# N303-3V1_0.net
KiCad netlist of a schematic drawn in Altium Designer
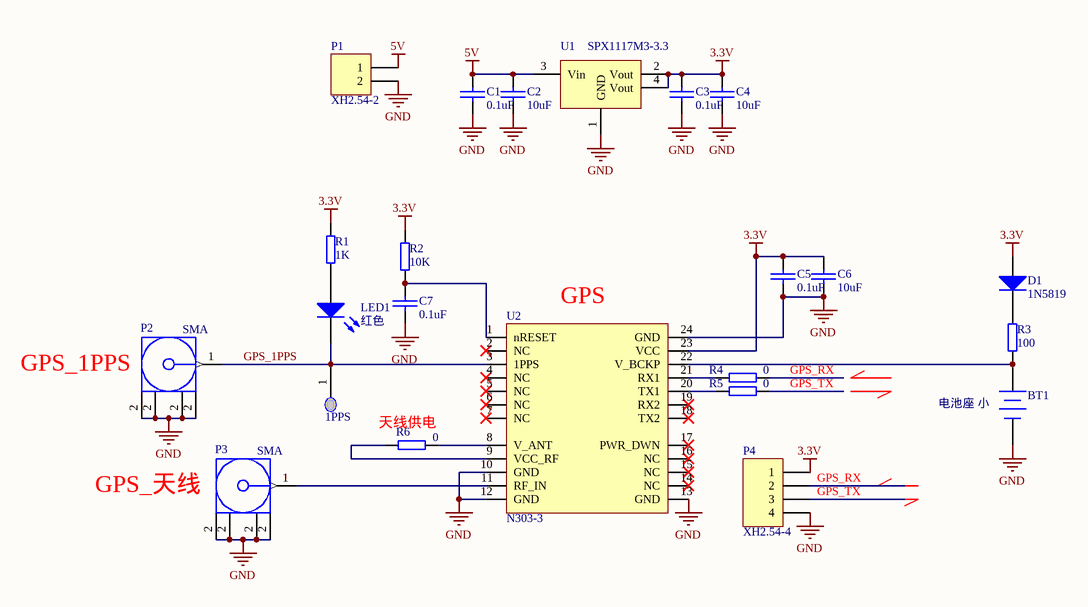
[diagram p0: N303-3V1.0.schdoc]

(export (version "E")
  (design (tool "Eeschema 10.0.6"))
  (components
    (comp (ref "1PPS")
      (value "TEST")
      (footprint "测试点（圆形）")
      (libsource (lib "Sch_Device_veryaz") (part "测试点_小"))
    )
    (comp (ref "BT1")
      (value "电池座 小")
      (footprint "电池座 2032 贴片 BS-8")
      (fields (field (name "PUBLISHER") "Altium Limited"))
      (libsource (lib "Sch_Device_veryaz") (part "电池座 小"))
    )
    (comp (ref "C1")
      (value "0.1uF")
      (footprint "0805")
      (libsource (lib "Sch_Device_veryaz") (part "电容 贴片 0805"))
    )
    (comp (ref "C2")
      (value "10uF")
      (footprint "1206")
      (libsource (lib "Sch_Device_veryaz") (part "电容 贴片 0805"))
    )
    (comp (ref "C3")
      (value "0.1uF")
      (footprint "0805")
      (libsource (lib "Sch_Device_veryaz") (part "电容 贴片 0805"))
    )
    (comp (ref "C4")
      (value "10uF")
      (footprint "1206")
      (libsource (lib "Sch_Device_veryaz") (part "电容 贴片 0805"))
    )
    (comp (ref "C5")
      (value "0.1uF")
      (footprint "0805")
      (libsource (lib "Sch_Device_veryaz") (part "电容 贴片 0805"))
    )
    (comp (ref "C6")
      (value "10uF")
      (footprint "1206")
      (libsource (lib "Sch_Device_veryaz") (part "电容 贴片 0805"))
    )
    (comp (ref "C7")
      (value "0.1uF")
      (footprint "0805")
      (libsource (lib "Sch_Device_veryaz") (part "电容 贴片 0805"))
    )
    (comp (ref "D1")
      (value "1N5819")
      (footprint "二极管 贴片 IN4148")
      (libsource (lib "Sch_Device_veryaz") (part "二极管 贴片 1N4148"))
    )
    (comp (ref "LED1")
      (value "红色")
      (footprint "LED5_单色")
      (libsource (lib "Sch_Device_veryaz") (part "贴片发光二极管 0805"))
    )
    (comp (ref "P1")
      (value "XH2.54-2")
      (footprint "VH2.54_2")
      (libsource (lib "Sch_Device_veryaz") (part "连接件 XH2.54-2"))
    )
    (comp (ref "P2")
      (value "SMA")
      (footprint "天线座 50ohm 直立")
      (libsource (lib "Sch_Device_veryaz") (part "联结件 天线座 SMA"))
    )
    (comp (ref "P3")
      (value "SMA")
      (footprint "天线座 50ohm 直立")
      (libsource (lib "Sch_Device_veryaz") (part "联结件 天线座 SMA"))
    )
    (comp (ref "P4")
      (value "XH2.54-4")
      (footprint "VH2.54_4")
      (libsource (lib "Sch_Device_veryaz") (part "联结件 XH2.54-4"))
    )
    (comp (ref "R1") (value "1K") (footprint "0805") (libsource (lib "") (part "电阻 贴片 0805_1")))
    (comp (ref "R2") (value "10K") (footprint "0805") (libsource (lib "") (part "电阻 贴片 0805_1")))
    (comp (ref "R3") (value "100") (footprint "0805") (libsource (lib "") (part "电阻 贴片 0805_1")))
    (comp (ref "R4") (value "0") (footprint "0805") (libsource (lib "Sch_Device_veryaz") (part "电阻 贴片 0805")))
    (comp (ref "R5") (value "0") (footprint "0805") (libsource (lib "Sch_Device_veryaz") (part "电阻 贴片 0805")))
    (comp (ref "R6") (value "0") (footprint "0805") (libsource (lib "Sch_Device_veryaz") (part "电阻 贴片 0805")))
    (comp (ref "U1")
      (value "SPX1117M3-3.3")
      (footprint "SOT223")
      (description "LDO")
      (libsource (lib "Sch_Device_veryaz") (part "贴片芯片 SPX1117M3-3.3"))
    )
    (comp (ref "U2")
      (value "N303-3")
      (footprint "模块 N303-3")
      (libsource (lib "Sch_Device_veryaz") (part "模块 N303-3"))
    )
  )
  (nets
    (net (code "1") (name "/GPS_1PPS") (class "Default")
      (node (ref "1PPS") (pin "1") (pinfunction "1_1") (pintype "passive"))
      (node (ref "LED1") (pin "2") (pinfunction "K_2") (pintype "passive"))
      (node (ref "P2") (pin "1") (pinfunction "Signal_1") (pintype "output"))
      (node (ref "U2") (pin "3") (pinfunction "1PPS_3") (pintype "passive"))
    )
    (net (code "2") (name "/GPS_RX") (class "Default")
      (node (ref "P4") (pin "2") (pinfunction "2_2") (pintype "passive"))
      (node (ref "R4") (pin "1") (pinfunction "1_1") (pintype "passive"))
    )
    (net (code "3") (name "/GPS_TX") (class "Default")
      (node (ref "P4") (pin "3") (pinfunction "3_3") (pintype "passive"))
      (node (ref "R5") (pin "1") (pinfunction "1_1") (pintype "passive"))
    )
    (net (code "4") (name "3.3V") (class "Default")
      (node (ref "C3") (pin "2") (pintype "passive"))
      (node (ref "C4") (pin "2") (pintype "passive"))
      (node (ref "C5") (pin "2") (pintype "passive"))
      (node (ref "C6") (pin "2") (pintype "passive"))
      (node (ref "D1") (pin "1") (pinfunction "A_1") (pintype "passive"))
      (node (ref "P4") (pin "1") (pinfunction "1_1") (pintype "passive"))
      (node (ref "R1") (pin "1") (pinfunction "1_1") (pintype "passive"))
      (node (ref "R2") (pin "1") (pinfunction "1_1") (pintype "passive"))
      (node (ref "U1") (pin "2") (pinfunction "Vout_2") (pintype "passive"))
      (node (ref "U1") (pin "4") (pinfunction "Vout_4") (pintype "passive"))
      (node (ref "U2") (pin "23") (pinfunction "VCC_23") (pintype "passive"))
    )
    (net (code "5") (name "5V") (class "Default")
      (node (ref "C1") (pin "2") (pintype "passive"))
      (node (ref "C2") (pin "2") (pintype "passive"))
      (node (ref "P1") (pin "1") (pinfunction "1_1") (pintype "passive"))
      (node (ref "U1") (pin "3") (pinfunction "Vin_3") (pintype "passive"))
    )
    (net (code "6") (name "GND") (class "Default")
      (node (ref "BT1") (pin "2") (pinfunction "-_2") (pintype "passive"))
      (node (ref "C1") (pin "1") (pintype "passive"))
      (node (ref "C2") (pin "1") (pintype "passive"))
      (node (ref "C3") (pin "1") (pintype "passive"))
      (node (ref "C4") (pin "1") (pintype "passive"))
      (node (ref "C5") (pin "1") (pintype "passive"))
      (node (ref "C6") (pin "1") (pintype "passive"))
      (node (ref "C7") (pin "1") (pintype "passive"))
      (node (ref "P1") (pin "2") (pinfunction "2_2") (pintype "passive"))
      (node (ref "P2") (pin "2") (pinfunction "2_2") (pintype "power_in"))
      (node (ref "P3") (pin "2") (pinfunction "2_2") (pintype "power_in"))
      (node (ref "P4") (pin "4") (pinfunction "4_4") (pintype "passive"))
      (node (ref "U1") (pin "1") (pinfunction "GND_1") (pintype "passive"))
      (node (ref "U2") (pin "10") (pinfunction "GND_10") (pintype "passive"))
      (node (ref "U2") (pin "12") (pinfunction "GND_12") (pintype "passive"))
      (node (ref "U2") (pin "13") (pinfunction "GND_13") (pintype "passive"))
      (node (ref "U2") (pin "24") (pinfunction "GND_24") (pintype "passive"))
    )
    (net (code "7") (name "Net-(BT1-+)") (class "Default")
      (node (ref "BT1") (pin "1") (pinfunction "+_1") (pintype "passive"))
      (node (ref "R3") (pin "2") (pinfunction "2_2") (pintype "passive"))
      (node (ref "U2") (pin "22") (pinfunction "V_BCKP_22") (pintype "passive"))
    )
    (net (code "8") (name "Net-(D1-K)") (class "Default")
      (node (ref "D1") (pin "2") (pinfunction "K_2") (pintype "passive"))
      (node (ref "R3") (pin "1") (pinfunction "1_1") (pintype "passive"))
    )
    (net (code "9") (name "Net-(LED1-A)") (class "Default")
      (node (ref "LED1") (pin "1") (pinfunction "A_1") (pintype "passive"))
      (node (ref "R1") (pin "2") (pinfunction "2_2") (pintype "passive"))
    )
    (net (code "10") (name "Net-(P3-Signal)") (class "Default")
      (node (ref "P3") (pin "1") (pinfunction "Signal_1") (pintype "output"))
      (node (ref "U2") (pin "11") (pinfunction "RF_IN_11") (pintype "passive"))
    )
    (net (code "11") (name "Net-(U2-RX1)") (class "Default")
      (node (ref "R4") (pin "2") (pinfunction "2_2") (pintype "passive"))
      (node (ref "U2") (pin "21") (pinfunction "RX1_21") (pintype "passive"))
    )
    (net (code "12") (name "Net-(U2-TX1)") (class "Default")
      (node (ref "R5") (pin "2") (pinfunction "2_2") (pintype "passive"))
      (node (ref "U2") (pin "20") (pinfunction "TX1_20") (pintype "passive"))
    )
    (net (code "13") (name "Net-(U2-VCC_RF)") (class "Default")
      (node (ref "R6") (pin "2") (pinfunction "2_2") (pintype "passive"))
      (node (ref "U2") (pin "9") (pinfunction "VCC_RF_9") (pintype "passive"))
    )
    (net (code "14") (name "Net-(U2-V_ANT)") (class "Default")
      (node (ref "R6") (pin "1") (pinfunction "1_1") (pintype "passive"))
      (node (ref "U2") (pin "8") (pinfunction "V_ANT_8") (pintype "passive"))
    )
    (net (code "15") (name "Net-(U2-nRESET)") (class "Default")
      (node (ref "C7") (pin "2") (pintype "passive"))
      (node (ref "R2") (pin "2") (pinfunction "2_2") (pintype "passive"))
      (node (ref "U2") (pin "1") (pinfunction "nRESET_1") (pintype "passive"))
    )
    (net (code "16") (name "unconnected-(U2-NC-Pad2)") (class "Default")
      (node (ref "U2") (pin "2") (pinfunction "NC_2") (pintype "passive+no_connect"))
    )
    (net (code "17") (name "unconnected-(U2-NC-Pad4)") (class "Default")
      (node (ref "U2") (pin "4") (pinfunction "NC_4") (pintype "passive+no_connect"))
    )
    (net (code "18") (name "unconnected-(U2-NC-Pad5)") (class "Default")
      (node (ref "U2") (pin "5") (pinfunction "NC_5") (pintype "passive+no_connect"))
    )
    (net (code "19") (name "unconnected-(U2-NC-Pad6)") (class "Default")
      (node (ref "U2") (pin "6") (pinfunction "NC_6") (pintype "passive+no_connect"))
    )
    (net (code "20") (name "unconnected-(U2-NC-Pad7)") (class "Default")
      (node (ref "U2") (pin "7") (pinfunction "NC_7") (pintype "passive+no_connect"))
    )
    (net (code "21") (name "unconnected-(U2-NC-Pad14)") (class "Default")
      (node (ref "U2") (pin "14") (pinfunction "NC_14") (pintype "passive+no_connect"))
    )
    (net (code "22") (name "unconnected-(U2-NC-Pad15)") (class "Default")
      (node (ref "U2") (pin "15") (pinfunction "NC_15") (pintype "passive+no_connect"))
    )
    (net (code "23") (name "unconnected-(U2-NC-Pad16)") (class "Default")
      (node (ref "U2") (pin "16") (pinfunction "NC_16") (pintype "passive+no_connect"))
    )
    (net (code "24") (name "unconnected-(U2-PWR_DWN-Pad17)") (class "Default")
      (node (ref "U2") (pin "17") (pinfunction "PWR_DWN_17") (pintype "passive+no_connect"))
    )
    (net (code "25") (name "unconnected-(U2-RX2-Pad19)") (class "Default")
      (node (ref "U2") (pin "19") (pinfunction "RX2_19") (pintype "passive+no_connect"))
    )
    (net (code "26") (name "unconnected-(U2-TX2-Pad18)") (class "Default")
      (node (ref "U2") (pin "18") (pinfunction "TX2_18") (pintype "passive+no_connect"))
    )
  )
)
